# power.net
KiCad netlist of a schematic drawn in Altium Designer
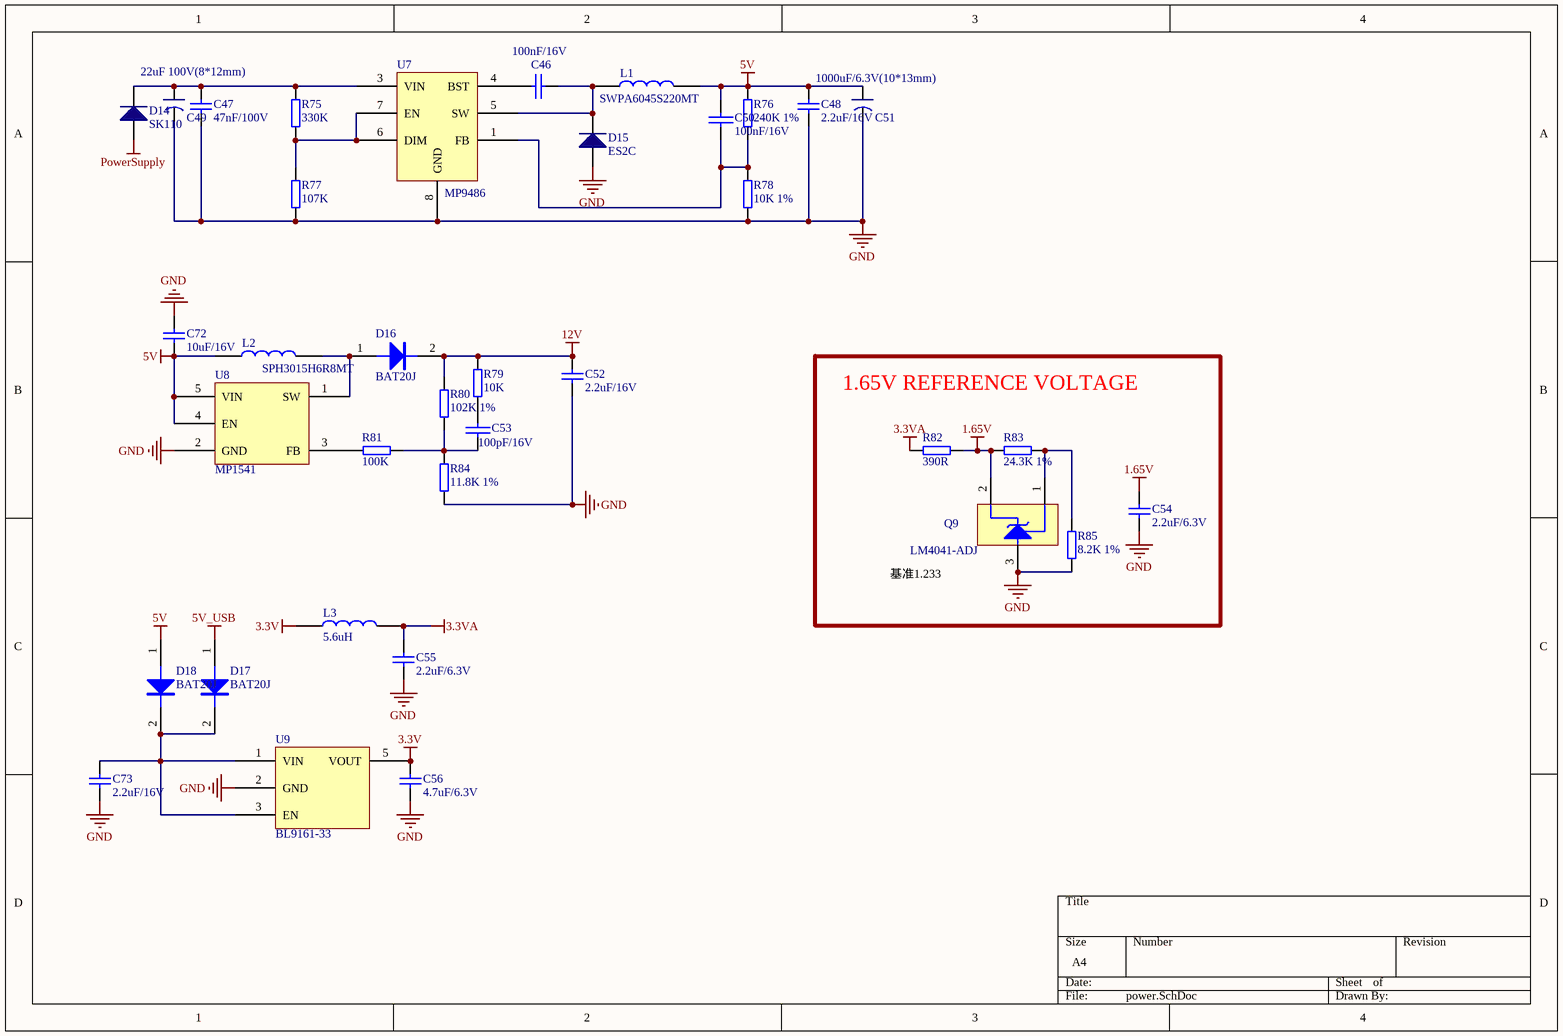
[diagram p0: power.SchDoc]

(export (version "E")
  (design (tool "Eeschema 10.0.6"))
  (components
    (comp (ref "C46")
      (value "100nF/16V")
      (footprint "C0402")
      (description "Capacitor")
      (libsource (lib "*") (part "CAP"))
    )
    (comp (ref "C47") (value "47nF/100V") (footprint "C1206") (libsource (lib "zijianku") (part "cap")))
    (comp (ref "C48") (value "2.2uF/16V") (footprint "C0603") (libsource (lib "zijianku") (part "cap")))
    (comp (ref "C49")
      (value "22uF 100V(8*12mm)")
      (footprint "AL-ELEC 8*12mm")
      (description "铝电解电容")
      (libsource (lib "Common Device") (part "Capacitor"))
    )
    (comp (ref "C50")
      (value "100nF/16V")
      (footprint "C0402")
      (description "Capacitor")
      (libsource (lib "*") (part "CAP"))
    )
    (comp (ref "C51")
      (value "1000uF/6.3V(10*13mm)")
      (footprint "AL-ELEC 10*13mm")
      (description "铝电解电容")
      (libsource (lib "Common Device") (part "Capacitor"))
    )
    (comp (ref "C52") (value "2.2uF/16V") (footprint "C0603") (libsource (lib "zijianku") (part "cap")))
    (comp (ref "C53")
      (value "100pF/16V")
      (footprint "C0402")
      (description "Capacitor")
      (libsource (lib "*") (part "CAP"))
    )
    (comp (ref "C54") (value "2.2uF/6.3V") (footprint "C0402") (libsource (lib "zijianku") (part "cap")))
    (comp (ref "C55") (value "2.2uF/6.3V") (footprint "C0402") (libsource (lib "zijianku") (part "cap")))
    (comp (ref "C56") (value "4.7uF/6.3V") (footprint "C0603") (libsource (lib "zijianku") (part "cap")))
    (comp (ref "C72") (value "10uF/16V") (footprint "C0805") (libsource (lib "zijianku") (part "cap")))
    (comp (ref "C73") (value "2.2uF/16V") (footprint "C0603") (libsource (lib "zijianku") (part "cap")))
    (comp (ref "D14")
      (value "SK110")
      (footprint "DO-214AC SMA")
      (libsource (lib "Common Device") (part "Diode"))
    )
    (comp (ref "D15")
      (value "ES2C")
      (footprint "DO-214AA SMB")
      (libsource (lib "Common Device") (part "Diode"))
    )
    (comp (ref "D16") (value "BAT20J") (footprint "SOD-323") (libsource (lib "*") (part "DIODE")))
    (comp (ref "D17") (value "BAT20J") (footprint "SOD-323") (libsource (lib "*") (part "DIODE")))
    (comp (ref "D18") (value "BAT20J") (footprint "SOD-323") (libsource (lib "*") (part "DIODE")))
    (comp (ref "L1")
      (value "SWPA6045S220MT")
      (footprint "SWPA6045S")
      (description "顺络 22uH")
      (libsource (lib "zijianku") (part "INDUCTOR"))
    )
    (comp (ref "L2")
      (value "SPH3015H6R8MT")
      (footprint "SPH3015")
      (description "顺络 6.8uH")
      (libsource (lib "zijianku") (part "INDUCTOR"))
    )
    (comp (ref "L3")
      (value "5.6uH")
      (footprint "L0402")
      (description "贴片电感")
      (libsource (lib "zijianku") (part "INDUCTOR"))
    )
    (comp (ref "Q9") (value "LM4041-ADJ") (footprint "SOT-23") (libsource (lib "*") (part "3CCCCCC")))
    (comp (ref "R75") (value "330K") (footprint "R0402") (libsource (lib "zijianku") (part "Resistance")))
    (comp (ref "R76") (value "240K 1%") (footprint "R0402") (libsource (lib "zijianku") (part "Resistance")))
    (comp (ref "R77") (value "107K") (footprint "R0402") (libsource (lib "zijianku") (part "Resistance")))
    (comp (ref "R78") (value "10K 1%") (footprint "R0402") (libsource (lib "zijianku") (part "Resistance")))
    (comp (ref "R79") (value "10K") (footprint "R0402") (libsource (lib "zijianku") (part "Resistance")))
    (comp (ref "R80") (value "102K 1%") (footprint "R0402") (libsource (lib "zijianku") (part "Resistance")))
    (comp (ref "R81") (value "100K") (footprint "R0402") (libsource (lib "zijianku") (part "Resistance")))
    (comp (ref "R82") (value "390R") (footprint "R0603") (libsource (lib "zijianku") (part "Resistance")))
    (comp (ref "R83") (value "24.3K 1%") (footprint "R0402") (libsource (lib "zijianku") (part "Resistance")))
    (comp (ref "R84") (value "11.8K 1%") (footprint "R0402") (libsource (lib "zijianku") (part "Resistance")))
    (comp (ref "R85") (value "8.2K 1%") (footprint "R0402") (libsource (lib "zijianku") (part "Resistance")))
    (comp (ref "U7") (value "MP9486") (footprint "SOIC-8 EP") (libsource (lib "zijianku") (part "MP9486")))
    (comp (ref "U8") (value "MP1541") (footprint "SOT-23(5)") (libsource (lib "zijianku") (part "MP1541")))
    (comp (ref "U9") (value "BL9161-33") (footprint "SOT-23(5)") (libsource (lib "zijianku") (part "BL9161")))
  )
  (nets
    (net (code "1") (name "1.65V") (class "Default")
      (node (ref "C54") (pin "2") (pinfunction "1_2") (pintype "passive"))
      (node (ref "Q9") (pin "2") (pintype "passive"))
      (node (ref "R82") (pin "2") (pintype "passive"))
      (node (ref "R83") (pin "1") (pintype "passive"))
    )
    (net (code "2") (name "3.3V") (class "Default")
      (node (ref "C56") (pin "2") (pinfunction "1_2") (pintype "passive"))
      (node (ref "L3") (pin "1") (pinfunction "1_1") (pintype "passive"))
      (node (ref "U9") (pin "5") (pinfunction "VOUT_5") (pintype "passive"))
    )
    (net (code "3") (name "3.3VA") (class "Default")
      (node (ref "C55") (pin "2") (pinfunction "1_2") (pintype "passive"))
      (node (ref "L3") (pin "2") (pinfunction "2_2") (pintype "passive"))
      (node (ref "R82") (pin "1") (pintype "passive"))
    )
    (net (code "4") (name "5V") (class "Default")
      (node (ref "C48") (pin "2") (pinfunction "1_2") (pintype "passive"))
      (node (ref "C50") (pin "1") (pinfunction "1_1") (pintype "passive"))
      (node (ref "C51") (pin "1") (pinfunction "0_1") (pintype "passive"))
      (node (ref "C72") (pin "1") (pinfunction "0_1") (pintype "passive"))
      (node (ref "D18") (pin "1") (pinfunction "A_1") (pintype "passive"))
      (node (ref "L1") (pin "2") (pinfunction "2_2") (pintype "passive"))
      (node (ref "L2") (pin "1") (pinfunction "1_1") (pintype "passive"))
      (node (ref "R76") (pin "1") (pintype "passive"))
      (node (ref "U8") (pin "4") (pinfunction "EN_4") (pintype "passive"))
      (node (ref "U8") (pin "5") (pinfunction "VIN_5") (pintype "passive"))
    )
    (net (code "5") (name "5V_USB") (class "Default")
      (node (ref "D17") (pin "1") (pinfunction "A_1") (pintype "passive"))
    )
    (net (code "6") (name "12V") (class "Default")
      (node (ref "C52") (pin "2") (pinfunction "1_2") (pintype "passive"))
      (node (ref "D16") (pin "2") (pinfunction "K_2") (pintype "passive"))
      (node (ref "R79") (pin "1") (pintype "passive"))
      (node (ref "R80") (pin "1") (pintype "passive"))
    )
    (net (code "7") (name "GND") (class "Default")
      (node (ref "C47") (pin "1") (pinfunction "0_1") (pintype "passive"))
      (node (ref "C48") (pin "1") (pinfunction "0_1") (pintype "passive"))
      (node (ref "C49") (pin "2") (pinfunction "1_2") (pintype "passive"))
      (node (ref "C51") (pin "2") (pinfunction "1_2") (pintype "passive"))
      (node (ref "C52") (pin "1") (pinfunction "0_1") (pintype "passive"))
      (node (ref "C54") (pin "1") (pinfunction "0_1") (pintype "passive"))
      (node (ref "C55") (pin "1") (pinfunction "0_1") (pintype "passive"))
      (node (ref "C56") (pin "1") (pinfunction "0_1") (pintype "passive"))
      (node (ref "C72") (pin "2") (pinfunction "1_2") (pintype "passive"))
      (node (ref "C73") (pin "1") (pinfunction "0_1") (pintype "passive"))
      (node (ref "D15") (pin "1") (pinfunction "0_1") (pintype "passive"))
      (node (ref "Q9") (pin "3") (pintype "passive"))
      (node (ref "R77") (pin "2") (pintype "passive"))
      (node (ref "R78") (pin "2") (pintype "passive"))
      (node (ref "R84") (pin "2") (pintype "passive"))
      (node (ref "R85") (pin "2") (pintype "passive"))
      (node (ref "U7") (pin "8") (pinfunction "GND_8") (pintype "passive"))
      (node (ref "U8") (pin "2") (pinfunction "GND_2") (pintype "passive"))
      (node (ref "U9") (pin "2") (pinfunction "GND_2") (pintype "passive"))
    )
    (net (code "8") (name "Net-(C47-1)") (class "Default")
      (node (ref "C47") (pin "2") (pinfunction "1_2") (pintype "passive"))
      (node (ref "C49") (pin "1") (pinfunction "0_1") (pintype "passive"))
      (node (ref "D14") (pin "2") (pinfunction "1_2") (pintype "passive"))
      (node (ref "R75") (pin "1") (pintype "passive"))
      (node (ref "U7") (pin "3") (pinfunction "VIN_3") (pintype "passive"))
    )
    (net (code "9") (name "Net-(C53-Pad1)") (class "Default")
      (node (ref "C53") (pin "1") (pinfunction "1_1") (pintype "passive"))
      (node (ref "R80") (pin "2") (pintype "passive"))
      (node (ref "R81") (pin "2") (pintype "passive"))
      (node (ref "R84") (pin "1") (pintype "passive"))
    )
    (net (code "10") (name "Net-(C53-Pad2)") (class "Default")
      (node (ref "C53") (pin "2") (pinfunction "2_2") (pintype "passive"))
      (node (ref "R79") (pin "2") (pintype "passive"))
    )
    (net (code "11") (name "Net-(C73-1)") (class "Default")
      (node (ref "C73") (pin "2") (pinfunction "1_2") (pintype "passive"))
      (node (ref "D17") (pin "2") (pinfunction "K_2") (pintype "passive"))
      (node (ref "D18") (pin "2") (pinfunction "K_2") (pintype "passive"))
      (node (ref "U9") (pin "1") (pinfunction "VIN_1") (pintype "passive"))
      (node (ref "U9") (pin "3") (pinfunction "EN_3") (pintype "passive"))
    )
    (net (code "12") (name "Net-(D15-1)") (class "Default")
      (node (ref "C46") (pin "1") (pinfunction "1_1") (pintype "passive"))
      (node (ref "D15") (pin "2") (pinfunction "1_2") (pintype "passive"))
      (node (ref "L1") (pin "1") (pinfunction "1_1") (pintype "passive"))
      (node (ref "U7") (pin "5") (pinfunction "SW_5") (pintype "passive"))
    )
    (net (code "13") (name "Net-(D16-A)") (class "Default")
      (node (ref "D16") (pin "1") (pinfunction "A_1") (pintype "passive"))
      (node (ref "L2") (pin "2") (pinfunction "2_2") (pintype "passive"))
      (node (ref "U8") (pin "1") (pinfunction "SW_1") (pintype "passive"))
    )
    (net (code "14") (name "Net-(Q9-Pad1)") (class "Default")
      (node (ref "Q9") (pin "1") (pinfunction "1_1") (pintype "passive"))
      (node (ref "R83") (pin "2") (pintype "passive"))
      (node (ref "R85") (pin "1") (pintype "passive"))
    )
    (net (code "15") (name "Net-(U7-BST)") (class "Default")
      (node (ref "C46") (pin "2") (pinfunction "2_2") (pintype "passive"))
      (node (ref "U7") (pin "4") (pinfunction "BST_4") (pintype "passive"))
    )
    (net (code "16") (name "Net-(U7-DIM)") (class "Default")
      (node (ref "R75") (pin "2") (pintype "passive"))
      (node (ref "R77") (pin "1") (pintype "passive"))
      (node (ref "U7") (pin "6") (pinfunction "DIM_6") (pintype "passive"))
      (node (ref "U7") (pin "7") (pinfunction "EN_7") (pintype "passive"))
    )
    (net (code "17") (name "Net-(U7-FB)") (class "Default")
      (node (ref "C50") (pin "2") (pinfunction "2_2") (pintype "passive"))
      (node (ref "R76") (pin "2") (pintype "passive"))
      (node (ref "R78") (pin "1") (pintype "passive"))
      (node (ref "U7") (pin "1") (pinfunction "FB_1") (pintype "passive"))
    )
    (net (code "18") (name "Net-(U8-FB)") (class "Default")
      (node (ref "R81") (pin "1") (pintype "passive"))
      (node (ref "U8") (pin "3") (pinfunction "FB_3") (pintype "passive"))
    )
    (net (code "19") (name "PowerSupply") (class "Default")
      (node (ref "D14") (pin "1") (pinfunction "0_1") (pintype "passive"))
    )
  )
)
